# ESP32_Board.net
KiCad netlist of a schematic drawn in Altium Designer
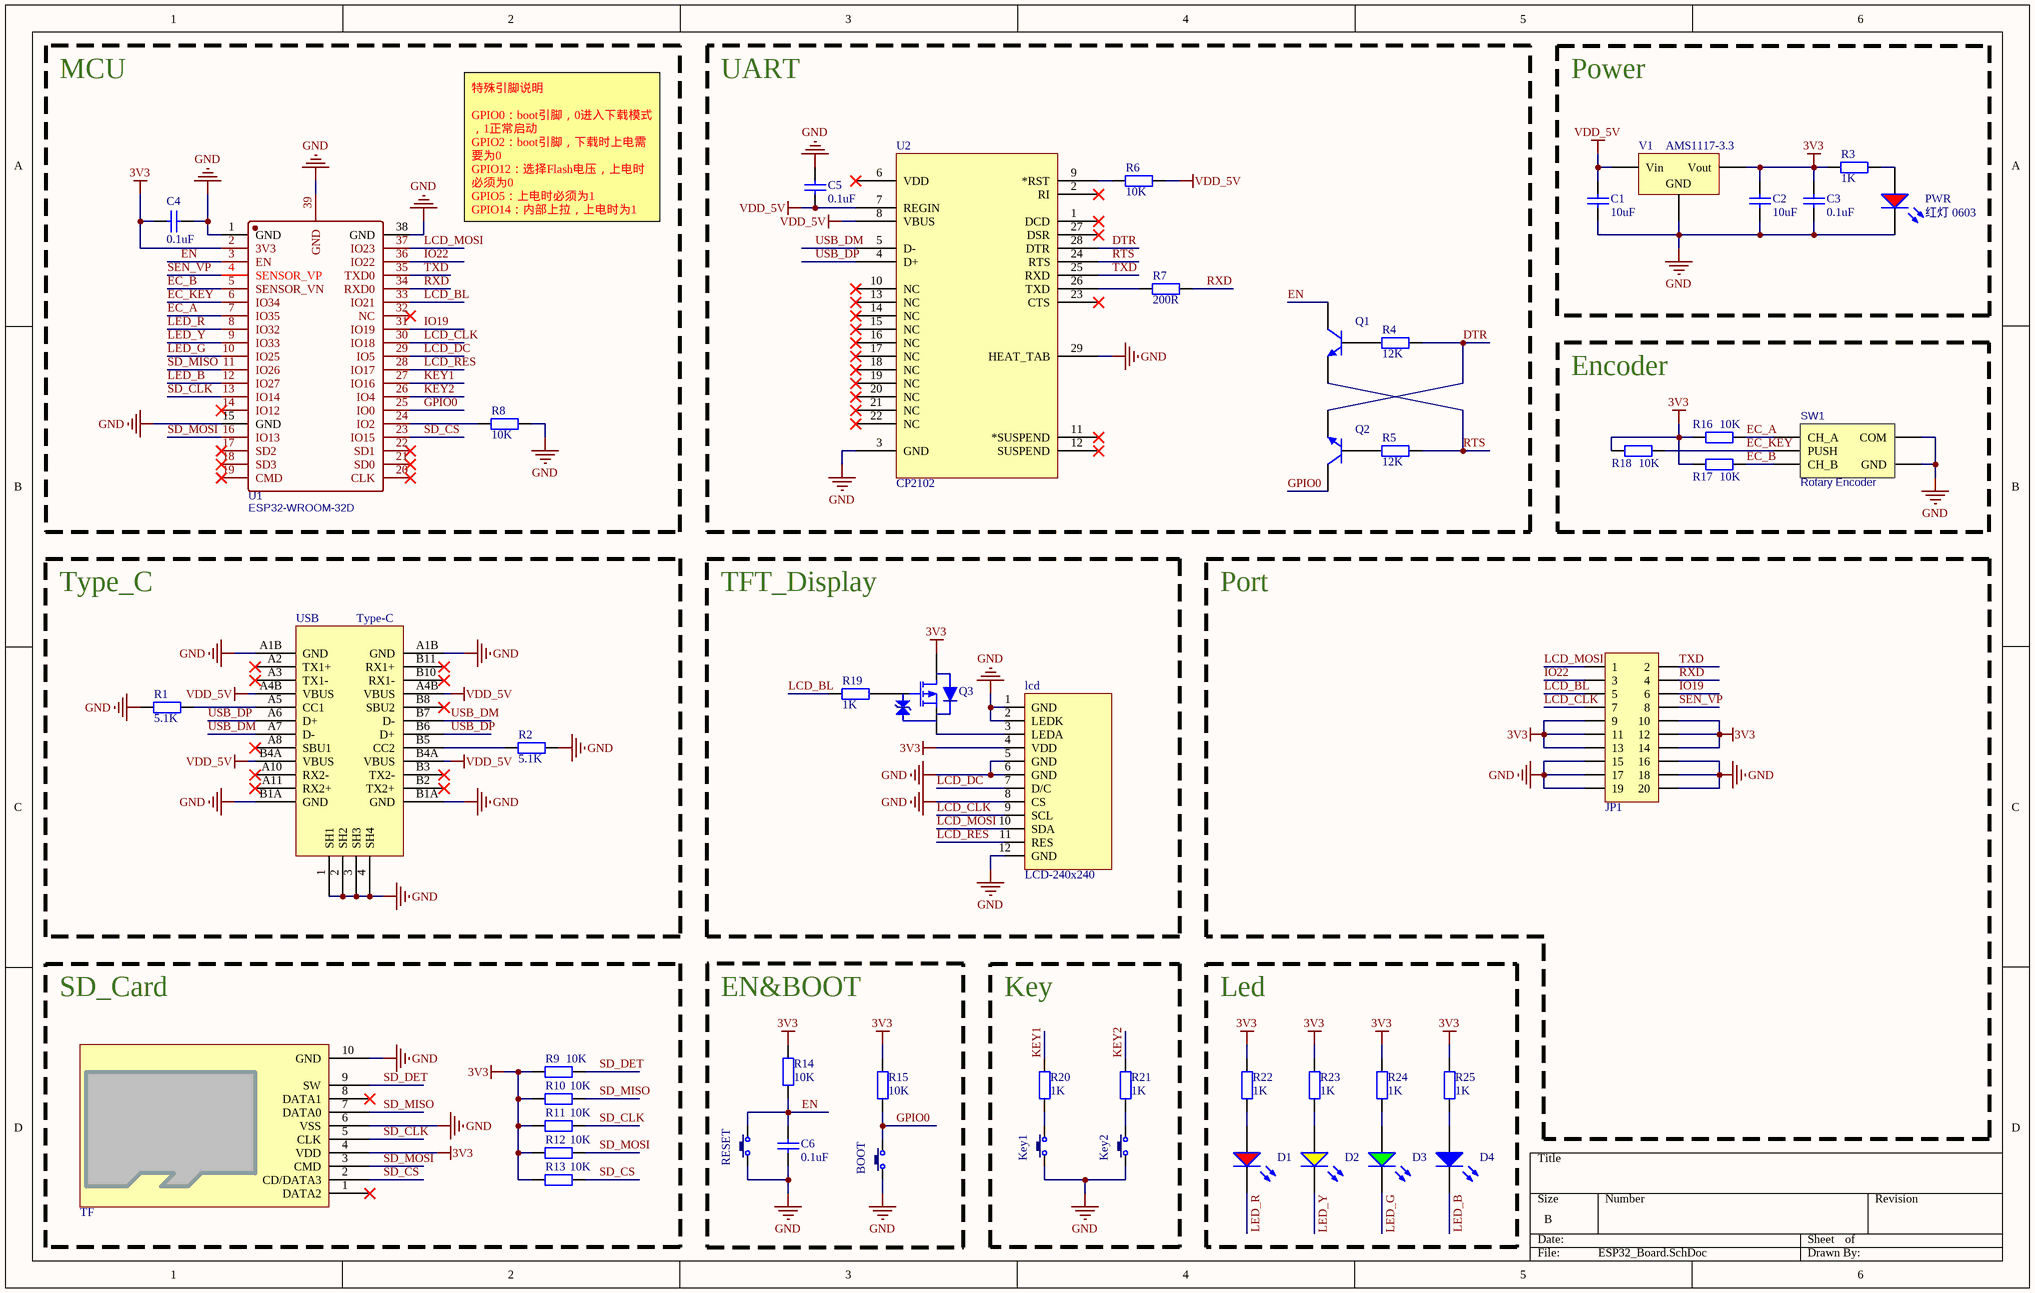
[diagram p0: ESP32_Board.SchDoc]

(export (version "E")
  (design (tool "Eeschema 10.0.6"))
  (components
    (comp (ref "BOOT")
      (value "3x6x5")
      (footprint "TSW SMD-6*6*5")
      (description "3x6轻触开关")
      (fields (field (name "版权归属") "源创客"))
      (libsource (lib "原理图库") (part "TSW 3x6"))
    )
    (comp (ref "C1")
      (value "10uF")
      (footprint "0603_C")
      (description "贴片电容")
      (libsource (lib "Miscellaneous Devices LC") (part "0603 1.2nF (122) 10% 50V"))
    )
    (comp (ref "C2")
      (value "10uF")
      (footprint "0603_C")
      (description "贴片电容")
      (libsource (lib "Miscellaneous Devices LC") (part "0603 1.2nF (122) 10% 50V"))
    )
    (comp (ref "C3")
      (value "0.1uF")
      (footprint "0603_C")
      (description "贴片电容")
      (libsource (lib "Miscellaneous Devices LC") (part "0603 1.2nF (122) 10% 50V"))
    )
    (comp (ref "C4")
      (value "0.1uF")
      (footprint "0603_C")
      (description "贴片电容")
      (libsource (lib "Miscellaneous Devices LC") (part "0603 1.2nF (122) 10% 50V"))
    )
    (comp (ref "C5")
      (value "0.1uF")
      (footprint "0603_C")
      (description "贴片电容")
      (libsource (lib "Miscellaneous Devices LC") (part "0603 100nF (104) 10% 50V"))
    )
    (comp (ref "C6")
      (value "0.1uF")
      (footprint "0603_C")
      (description "贴片电容")
      (libsource (lib "Miscellaneous Devices LC") (part "0603 10uF (106) 10% 10V"))
    )
    (comp (ref "D1")
      (value "红灯 0805")
      (footprint "0805_LED_S1")
      (description "发光二极管")
      (libsource (lib "Miscellaneous Devices LC") (part "0805 红灯"))
    )
    (comp (ref "D2")
      (value "黄灯 0805")
      (footprint "0805_LED_S1")
      (description "发光二极管")
      (libsource (lib "Miscellaneous Devices LC") (part "0805 黄灯"))
    )
    (comp (ref "D3")
      (value "翠绿 0805")
      (footprint "0805_LED_S1")
      (description "发光二极管")
      (libsource (lib "Miscellaneous Devices LC") (part "0805 翠绿"))
    )
    (comp (ref "D4")
      (value "蓝灯 0805")
      (footprint "0805_LED_S1")
      (description "发光二极管")
      (libsource (lib "Miscellaneous Devices LC") (part "0805 蓝灯"))
    )
    (comp (ref "JP1")
      (value "Header 2X10")
      (footprint "HDR2.54-M-LS-2x10P")
      (description "10*2P接插件")
      (fields (field (name "版权归属") "源创客"))
      (libsource (lib "Schlib1") (part "Header 10X2"))
    )
    (comp (ref "Key1")
      (value "3x6x5")
      (footprint "TSW SMD-6*6*5")
      (description "3x6轻触开关")
      (fields (field (name "版权归属") "源创客"))
      (libsource (lib "原理图库") (part "TSW 3x6"))
    )
    (comp (ref "Key2")
      (value "3x6x5")
      (footprint "TSW SMD-6*6*5")
      (description "3x6轻触开关")
      (fields (field (name "版权归属") "源创客"))
      (libsource (lib "原理图库") (part "TSW 3x6"))
    )
    (comp (ref "lcd")
      (value "LCD-240x240")
      (footprint "LCD-240x240-NoHole")
      (description "显示屏")
      (libsource (lib "Schlib1") (part "LCD-240x240"))
    )
    (comp (ref "PWR")
      (value "红灯 0603")
      (footprint "0603_LED_S1")
      (description "发光二极管")
      (libsource (lib "Miscellaneous Devices LC") (part "0603 红灯"))
    )
    (comp (ref "Q1")
      (value "SS8050 Y1")
      (footprint "SOT-23(SOT-23-3)")
      (description "三极管")
      (libsource (lib "Miscellaneous Devices LC") (part "SOT-23 SS8050 Y1"))
    )
    (comp (ref "Q2")
      (value "SS8050 Y1")
      (footprint "SOT-23(SOT-23-3)")
      (description "三极管")
      (libsource (lib "Miscellaneous Devices LC") (part "SOT-23 SS8050 Y1"))
    )
    (comp (ref "Q3")
      (value "AO3415A")
      (footprint "SOT23-3")
      (description "MOSFET")
      (fields (field (name "PUBLISHER") "Altium Limited"))
      (libsource (lib "Schlib1") (part "AO3415A"))
    )
    (comp (ref "R1")
      (value "5.1K")
      (footprint "0603_R")
      (description "贴片电阻")
      (libsource (lib "Miscellaneous Devices LC") (part "0603 1.1KΩ (1101) 1%"))
    )
    (comp (ref "R2")
      (value "5.1K")
      (footprint "0603_R")
      (description "贴片电阻")
      (libsource (lib "Miscellaneous Devices LC") (part "0603 1.1KΩ (1101) 1%"))
    )
    (comp (ref "R3")
      (value "1K")
      (footprint "0603_R")
      (description "贴片电阻")
      (libsource (lib "Miscellaneous Devices LC") (part "0603 110KΩ (1103) 1%"))
    )
    (comp (ref "R4")
      (value "12K")
      (footprint "0603_R")
      (description "贴片电阻")
      (libsource (lib "Miscellaneous Devices LC") (part "0603 1.2KΩ (1201) 1%"))
    )
    (comp (ref "R5")
      (value "12K")
      (footprint "0603_R")
      (description "贴片电阻")
      (libsource (lib "Miscellaneous Devices LC") (part "0603 1.2KΩ (1201) 1%"))
    )
    (comp (ref "R6")
      (value "10K")
      (footprint "0603_R")
      (description "贴片电阻")
      (libsource (lib "Miscellaneous Devices LC") (part "0603 1.2KΩ (1201) 1%"))
    )
    (comp (ref "R7")
      (value "200R")
      (footprint "0603_R")
      (description "贴片电阻")
      (libsource (lib "Miscellaneous Devices LC") (part "0603 1.2KΩ (1201) 1%"))
    )
    (comp (ref "R8")
      (value "10K")
      (footprint "0603_R")
      (description "贴片电阻")
      (libsource (lib "Miscellaneous Devices LC") (part "0603 1.5KΩ (1501) 1%"))
    )
    (comp (ref "R9")
      (value "10K")
      (footprint "0603_R")
      (description "贴片电阻")
      (libsource (lib "Miscellaneous Devices LC") (part "0603 1.8MΩ (1804) 1%"))
    )
    (comp (ref "R10")
      (value "10K")
      (footprint "0603_R")
      (description "贴片电阻")
      (libsource (lib "Miscellaneous Devices LC") (part "0603 1.8MΩ (1804) 1%"))
    )
    (comp (ref "R11")
      (value "10K")
      (footprint "0603_R")
      (description "贴片电阻")
      (libsource (lib "Miscellaneous Devices LC") (part "0603 1.8MΩ (1804) 1%"))
    )
    (comp (ref "R12")
      (value "10K")
      (footprint "0603_R")
      (description "贴片电阻")
      (libsource (lib "Miscellaneous Devices LC") (part "0603 1.8MΩ (1804) 1%"))
    )
    (comp (ref "R13")
      (value "10K")
      (footprint "0603_R")
      (description "贴片电阻")
      (libsource (lib "Miscellaneous Devices LC") (part "0603 1.8MΩ (1804) 1%"))
    )
    (comp (ref "R14")
      (value "10K")
      (footprint "0603_R")
      (description "贴片电阻")
      (libsource (lib "Miscellaneous Devices LC") (part "0603 100KΩ (1003) 1%"))
    )
    (comp (ref "R15")
      (value "10K")
      (footprint "0603_R")
      (description "贴片电阻")
      (libsource (lib "") (part "0603 1.5KΩ (1501) 1%_1"))
    )
    (comp (ref "R16")
      (value "10K")
      (footprint "0603_R")
      (description "贴片电阻")
      (libsource (lib "Miscellaneous Devices LC") (part "0603 1.8MΩ (1804) 1%"))
    )
    (comp (ref "R17")
      (value "10K")
      (footprint "0603_R")
      (description "贴片电阻")
      (libsource (lib "Miscellaneous Devices LC") (part "0603 1.8MΩ (1804) 1%"))
    )
    (comp (ref "R18")
      (value "10K")
      (footprint "0603_R")
      (description "贴片电阻")
      (libsource (lib "Miscellaneous Devices LC") (part "0603 1.8MΩ (1804) 1%"))
    )
    (comp (ref "R19")
      (value "1K")
      (footprint "0603_R")
      (description "贴片电阻")
      (libsource (lib "Miscellaneous Devices LC") (part "0603 1.2KΩ (1201) 1%"))
    )
    (comp (ref "R20")
      (value "1K")
      (footprint "0603_R")
      (description "贴片电阻")
      (libsource (lib "") (part "0603 1.2KΩ (1201) 1%_2"))
    )
    (comp (ref "R21")
      (value "1K")
      (footprint "0603_R")
      (description "贴片电阻")
      (libsource (lib "") (part "0603 1.2KΩ (1201) 1%_2"))
    )
    (comp (ref "R22")
      (value "1K")
      (footprint "0603_R")
      (description "贴片电阻")
      (libsource (lib "") (part "0603 1.2KΩ (1201) 1%_1"))
    )
    (comp (ref "R23")
      (value "1K")
      (footprint "0603_R")
      (description "贴片电阻")
      (libsource (lib "") (part "0603 1.2KΩ (1201) 1%_1"))
    )
    (comp (ref "R24")
      (value "1K")
      (footprint "0603_R")
      (description "贴片电阻")
      (libsource (lib "") (part "0603 1.2KΩ (1201) 1%_1"))
    )
    (comp (ref "R25")
      (value "1K")
      (footprint "0603_R")
      (description "贴片电阻")
      (libsource (lib "") (part "0603 1.2KΩ (1201) 1%_1"))
    )
    (comp (ref "RESET")
      (value "3x6x5")
      (footprint "SW")
      (description "3x6轻触开关")
      (fields (field (name "版权归属") "源创客"))
      (libsource (lib "原理图库") (part "TSW 3x6"))
    )
    (comp (ref "SW1")
      (value "Rotary Encoder")
      (footprint "SIQ-02FVS3")
      (fields
        (field (name "BOM_SUPPLIER PART") "C1322543")
        (field (name "BOM_MANUFACTURER PART") "EC11E1534443")
        (field (name "CONTRIBUTOR") "LCSC")
      )
      (libsource (lib "Schlib1") (part "Rotary Encoder"))
    )
    (comp (ref "TF")
      (value "TF")
      (footprint "Micro SD")
      (description "8脚自弹")
      (libsource (lib "原理图库") (part "TF卡座"))
    )
    (comp (ref "U1")
      (value "ESP32-WROOM-32D")
      (footprint "WIFI-SMD_ESP32-WROOM-32E")
      (fields
        (field (name "BOM_SUPPLIER PART") "C701342")
        (field (name "BOM_MANUFACTURER PART") "ESP32-WROOM-32E(8MB)")
        (field (name "CONTRIBUTOR") "LCSC")
      )
      (libsource (lib "原理图库") (part "ESP32_WROOM_32D"))
    )
    (comp (ref "U2")
      (value "CP2102")
      (footprint "QFN28 5x5_N")
      (description "USB转TTL")
      (libsource (lib "原理图库") (part "CP2102"))
    )
    (comp (ref "USB")
      (value "Type-C")
      (footprint "Type-C-TOP")
      (libsource (lib "原理图库") (part "USB-Type-C-TOP"))
    )
    (comp (ref "V1")
      (value "AMS1117-3.3")
      (footprint "SOT-89")
      (description "低压差线性稳压(LDO)")
      (libsource (lib "Miscellaneous Devices LC") (part "SOT-223 AMS1117-3.3"))
    )
  )
  (nets
    (net (code "1") (name "/DTR") (class "Default")
      (node (ref "Q2") (pin "2") (pinfunction "E_2") (pintype "passive"))
      (node (ref "R4") (pin "2") (pinfunction "2_2") (pintype "passive"))
      (node (ref "U2") (pin "28") (pinfunction "DTR_28") (pintype "passive"))
    )
    (net (code "2") (name "/EC_A") (class "Default")
      (node (ref "R16") (pin "2") (pinfunction "2_2") (pintype "passive"))
      (node (ref "SW1") (pin "1") (pinfunction "CH_A_1") (pintype "passive"))
      (node (ref "U1") (pin "7") (pinfunction "IO35_7") (pintype "passive"))
    )
    (net (code "3") (name "/EC_B") (class "Default")
      (node (ref "R17") (pin "2") (pinfunction "2_2") (pintype "passive"))
      (node (ref "SW1") (pin "4") (pinfunction "CH_B_4") (pintype "passive"))
      (node (ref "U1") (pin "5") (pinfunction "SENSOR_VN_5") (pintype "passive"))
    )
    (net (code "4") (name "/EC_KEY") (class "Default")
      (node (ref "R18") (pin "2") (pinfunction "2_2") (pintype "passive"))
      (node (ref "SW1") (pin "2") (pinfunction "PUSH_2") (pintype "passive"))
      (node (ref "U1") (pin "6") (pinfunction "IO34_6") (pintype "passive"))
    )
    (net (code "5") (name "/EN") (class "Default")
      (node (ref "C6") (pin "2") (pinfunction "2_2") (pintype "passive"))
      (node (ref "Q1") (pin "3") (pinfunction "C_3") (pintype "passive"))
      (node (ref "R14") (pin "1") (pinfunction "1_1") (pintype "passive"))
      (node (ref "RESET") (pin "2") (pinfunction "2_2") (pintype "passive"))
      (node (ref "U1") (pin "3") (pinfunction "EN_3") (pintype "passive"))
    )
    (net (code "6") (name "/GPIO0") (class "Default")
      (node (ref "BOOT") (pin "2") (pinfunction "2_2") (pintype "passive"))
      (node (ref "Q2") (pin "3") (pinfunction "C_3") (pintype "passive"))
      (node (ref "R15") (pin "1") (pinfunction "1_1") (pintype "passive"))
      (node (ref "U1") (pin "25") (pinfunction "IO0_25") (pintype "passive"))
    )
    (net (code "7") (name "/IO19") (class "Default")
      (node (ref "JP1") (pin "6") (pinfunction "6_6") (pintype "passive"))
      (node (ref "U1") (pin "31") (pinfunction "IO19_31") (pintype "passive"))
    )
    (net (code "8") (name "/IO22") (class "Default")
      (node (ref "JP1") (pin "3") (pinfunction "3_3") (pintype "passive"))
      (node (ref "U1") (pin "36") (pinfunction "IO22_36") (pintype "passive"))
    )
    (net (code "9") (name "/KEY1") (class "Default")
      (node (ref "R20") (pin "2") (pinfunction "2_2") (pintype "passive"))
      (node (ref "U1") (pin "27") (pinfunction "IO16_27") (pintype "passive"))
    )
    (net (code "10") (name "/KEY2") (class "Default")
      (node (ref "R21") (pin "2") (pinfunction "2_2") (pintype "passive"))
      (node (ref "U1") (pin "26") (pinfunction "IO4_26") (pintype "passive"))
    )
    (net (code "11") (name "/LCD_BL") (class "Default")
      (node (ref "JP1") (pin "5") (pinfunction "5_5") (pintype "passive"))
      (node (ref "R19") (pin "1") (pinfunction "1_1") (pintype "passive"))
      (node (ref "U1") (pin "33") (pinfunction "IO21_33") (pintype "passive"))
    )
    (net (code "12") (name "/LCD_CLK") (class "Default")
      (node (ref "JP1") (pin "7") (pinfunction "7_7") (pintype "passive"))
      (node (ref "U1") (pin "30") (pinfunction "IO18_30") (pintype "passive"))
      (node (ref "lcd") (pin "9") (pinfunction "SCL_9") (pintype "passive"))
    )
    (net (code "13") (name "/LCD_DC") (class "Default")
      (node (ref "U1") (pin "29") (pinfunction "IO5_29") (pintype "passive"))
      (node (ref "lcd") (pin "7") (pinfunction "D/C_7") (pintype "passive"))
    )
    (net (code "14") (name "/LCD_MOSI") (class "Default")
      (node (ref "JP1") (pin "1") (pinfunction "1_1") (pintype "passive"))
      (node (ref "U1") (pin "37") (pinfunction "IO23_37") (pintype "passive"))
      (node (ref "lcd") (pin "10") (pinfunction "SDA_10") (pintype "passive"))
    )
    (net (code "15") (name "/LCD_RES") (class "Default")
      (node (ref "U1") (pin "28") (pinfunction "IO17_28") (pintype "passive"))
      (node (ref "lcd") (pin "11") (pinfunction "RES_11") (pintype "passive"))
    )
    (net (code "16") (name "/LED_B") (class "Default")
      (node (ref "D4") (pin "K") (pinfunction "K_K") (pintype "passive"))
      (node (ref "U1") (pin "12") (pinfunction "IO27_12") (pintype "passive"))
    )
    (net (code "17") (name "/LED_G") (class "Default")
      (node (ref "D3") (pin "K") (pinfunction "K_K") (pintype "passive"))
      (node (ref "U1") (pin "10") (pinfunction "IO25_10") (pintype "passive"))
    )
    (net (code "18") (name "/LED_R") (class "Default")
      (node (ref "D1") (pin "K") (pinfunction "K_K") (pintype "passive"))
      (node (ref "U1") (pin "8") (pinfunction "IO32_8") (pintype "passive"))
    )
    (net (code "19") (name "/LED_Y") (class "Default")
      (node (ref "D2") (pin "K") (pinfunction "K_K") (pintype "passive"))
      (node (ref "U1") (pin "9") (pinfunction "IO33_9") (pintype "passive"))
    )
    (net (code "20") (name "/RTS") (class "Default")
      (node (ref "Q1") (pin "2") (pinfunction "E_2") (pintype "passive"))
      (node (ref "R5") (pin "2") (pinfunction "2_2") (pintype "passive"))
      (node (ref "U2") (pin "24") (pinfunction "RTS_24") (pintype "passive"))
    )
    (net (code "21") (name "/RXD") (class "Default")
      (node (ref "JP1") (pin "4") (pinfunction "4_4") (pintype "passive"))
      (node (ref "R7") (pin "2") (pinfunction "2_2") (pintype "passive"))
      (node (ref "U1") (pin "34") (pinfunction "RXD0_34") (pintype "passive"))
    )
    (net (code "22") (name "/SD_CLK") (class "Default")
      (node (ref "R11") (pin "2") (pinfunction "2_2") (pintype "passive"))
      (node (ref "TF") (pin "5") (pinfunction "CLK_5") (pintype "passive"))
      (node (ref "U1") (pin "13") (pinfunction "IO14_13") (pintype "passive"))
    )
    (net (code "23") (name "/SD_CS") (class "Default")
      (node (ref "R13") (pin "2") (pinfunction "2_2") (pintype "passive"))
      (node (ref "TF") (pin "2") (pinfunction "CD/DATA3_2") (pintype "passive"))
      (node (ref "U1") (pin "23") (pinfunction "IO15_23") (pintype "passive"))
    )
    (net (code "24") (name "/SD_DET") (class "Default")
      (node (ref "R9") (pin "2") (pinfunction "2_2") (pintype "passive"))
      (node (ref "TF") (pin "9") (pinfunction "SW_9") (pintype "passive"))
    )
    (net (code "25") (name "/SD_MISO") (class "Default")
      (node (ref "R10") (pin "2") (pinfunction "2_2") (pintype "passive"))
      (node (ref "TF") (pin "7") (pinfunction "DATA0_7") (pintype "passive"))
      (node (ref "U1") (pin "11") (pinfunction "IO26_11") (pintype "passive"))
    )
    (net (code "26") (name "/SD_MOSI") (class "Default")
      (node (ref "R12") (pin "2") (pinfunction "2_2") (pintype "passive"))
      (node (ref "TF") (pin "3") (pinfunction "CMD_3") (pintype "passive"))
      (node (ref "U1") (pin "16") (pinfunction "IO13_16") (pintype "passive"))
    )
    (net (code "27") (name "/SEN_VP") (class "Default")
      (node (ref "JP1") (pin "8") (pinfunction "8_8") (pintype "passive"))
      (node (ref "U1") (pin "4") (pinfunction "SENSOR_VP_4") (pintype "passive"))
    )
    (net (code "28") (name "/TXD") (class "Default")
      (node (ref "JP1") (pin "2") (pinfunction "2_2") (pintype "passive"))
      (node (ref "U1") (pin "35") (pinfunction "TXD0_35") (pintype "passive"))
      (node (ref "U2") (pin "25") (pinfunction "RXD_25") (pintype "passive"))
    )
    (net (code "29") (name "/USB_DM") (class "Default")
      (node (ref "U2") (pin "5") (pinfunction "D-_5") (pintype "passive"))
      (node (ref "USB") (pin "A7") (pinfunction "D-_A7") (pintype "passive"))
      (node (ref "USB") (pin "B7") (pinfunction "D-_B7") (pintype "passive"))
    )
    (net (code "30") (name "/USB_DP") (class "Default")
      (node (ref "U2") (pin "4") (pinfunction "D+_4") (pintype "passive"))
      (node (ref "USB") (pin "A6") (pinfunction "D+_A6") (pintype "passive"))
      (node (ref "USB") (pin "B6") (pinfunction "D+_B6") (pintype "passive"))
    )
    (net (code "31") (name "3V3") (class "Default")
      (node (ref "C2") (pin "2") (pinfunction "2_2") (pintype "passive"))
      (node (ref "C3") (pin "2") (pinfunction "2_2") (pintype "passive"))
      (node (ref "C4") (pin "2") (pinfunction "2_2") (pintype "passive"))
      (node (ref "JP1") (pin "10") (pinfunction "10_10") (pintype "passive"))
      (node (ref "JP1") (pin "11") (pinfunction "11_11") (pintype "passive"))
      (node (ref "JP1") (pin "12") (pinfunction "12_12") (pintype "passive"))
      (node (ref "JP1") (pin "13") (pinfunction "13_13") (pintype "passive"))
      (node (ref "JP1") (pin "14") (pinfunction "14_14") (pintype "passive"))
      (node (ref "JP1") (pin "9") (pinfunction "9_9") (pintype "passive"))
      (node (ref "Q3") (pin "3") (pinfunction "D_3") (pintype "passive"))
      (node (ref "R10") (pin "1") (pinfunction "1_1") (pintype "passive"))
      (node (ref "R11") (pin "1") (pinfunction "1_1") (pintype "passive"))
      (node (ref "R12") (pin "1") (pinfunction "1_1") (pintype "passive"))
      (node (ref "R13") (pin "1") (pinfunction "1_1") (pintype "passive"))
      (node (ref "R14") (pin "2") (pinfunction "2_2") (pintype "passive"))
      (node (ref "R15") (pin "2") (pinfunction "2_2") (pintype "passive"))
      (node (ref "R16") (pin "1") (pinfunction "1_1") (pintype "passive"))
      (node (ref "R17") (pin "1") (pinfunction "1_1") (pintype "passive"))
      (node (ref "R18") (pin "1") (pinfunction "1_1") (pintype "passive"))
      (node (ref "R22") (pin "1") (pinfunction "1_1") (pintype "passive"))
      (node (ref "R23") (pin "1") (pinfunction "1_1") (pintype "passive"))
      (node (ref "R24") (pin "1") (pinfunction "1_1") (pintype "passive"))
      (node (ref "R25") (pin "1") (pinfunction "1_1") (pintype "passive"))
      (node (ref "R3") (pin "1") (pinfunction "1_1") (pintype "passive"))
      (node (ref "R9") (pin "1") (pinfunction "1_1") (pintype "passive"))
      (node (ref "TF") (pin "4") (pinfunction "VDD_4") (pintype "passive"))
      (node (ref "U1") (pin "2") (pinfunction "3V3_2") (pintype "passive"))
      (node (ref "V1") (pin "2") (pinfunction "Vout_2") (pintype "passive"))
      (node (ref "lcd") (pin "4") (pinfunction "VDD_4") (pintype "passive"))
    )
    (net (code "32") (name "GND") (class "Default")
      (node (ref "BOOT") (pin "1") (pinfunction "1_1") (pintype "passive"))
      (node (ref "C1") (pin "1") (pinfunction "1_1") (pintype "passive"))
      (node (ref "C2") (pin "1") (pinfunction "1_1") (pintype "passive"))
      (node (ref "C3") (pin "1") (pinfunction "1_1") (pintype "passive"))
      (node (ref "C4") (pin "1") (pinfunction "1_1") (pintype "passive"))
      (node (ref "C5") (pin "2") (pinfunction "2_2") (pintype "passive"))
      (node (ref "C6") (pin "1") (pinfunction "1_1") (pintype "passive"))
      (node (ref "JP1") (pin "15") (pinfunction "15_15") (pintype "passive"))
      (node (ref "JP1") (pin "16") (pinfunction "16_16") (pintype "passive"))
      (node (ref "JP1") (pin "17") (pinfunction "17_17") (pintype "passive"))
      (node (ref "JP1") (pin "18") (pinfunction "18_18") (pintype "passive"))
      (node (ref "JP1") (pin "19") (pinfunction "19_19") (pintype "passive"))
      (node (ref "JP1") (pin "20") (pinfunction "20_20") (pintype "passive"))
      (node (ref "Key1") (pin "1") (pinfunction "1_1") (pintype "passive"))
      (node (ref "Key2") (pin "1") (pinfunction "1_1") (pintype "passive"))
      (node (ref "PWR") (pin "K") (pinfunction "K_K") (pintype "passive"))
      (node (ref "R1") (pin "1") (pinfunction "1_1") (pintype "passive"))
      (node (ref "R2") (pin "2") (pinfunction "2_2") (pintype "passive"))
      (node (ref "R8") (pin "2") (pinfunction "2_2") (pintype "passive"))
      (node (ref "RESET") (pin "1") (pinfunction "1_1") (pintype "passive"))
      (node (ref "SW1") (pin "3") (pinfunction "COM_3") (pintype "passive"))
      (node (ref "SW1") (pin "5") (pinfunction "GND_5") (pintype "passive"))
      (node (ref "TF") (pin "10") (pinfunction "GND_10") (pintype "passive"))
      (node (ref "TF") (pin "6") (pinfunction "VSS_6") (pintype "passive"))
      (node (ref "U1") (pin "1") (pinfunction "GND_1") (pintype "passive"))
      (node (ref "U1") (pin "15") (pinfunction "GND_15") (pintype "passive"))
      (node (ref "U1") (pin "38") (pinfunction "GND_38") (pintype "passive"))
      (node (ref "U1") (pin "39") (pinfunction "GND_39") (pintype "passive"))
      (node (ref "U2") (pin "29") (pinfunction "HEAT_TAB_29") (pintype "passive"))
      (node (ref "U2") (pin "3") (pinfunction "GND_3") (pintype "passive"))
      (node (ref "USB") (pin "1") (pinfunction "SH1_1") (pintype "passive"))
      (node (ref "USB") (pin "2") (pinfunction "SH2_2") (pintype "passive"))
      (node (ref "USB") (pin "3") (pinfunction "SH3_3") (pintype "passive"))
      (node (ref "USB") (pin "4") (pinfunction "SH4_4") (pintype "passive"))
      (node (ref "USB") (pin "A1B") (pinfunction "GND_A1B") (pintype "passive"))
      (node (ref "USB") (pin "B1A") (pinfunction "GND_B1A") (pintype "passive"))
      (node (ref "V1") (pin "1") (pinfunction "GND_1") (pintype "passive"))
      (node (ref "lcd") (pin "1") (pinfunction "GND_1") (pintype "passive"))
      (node (ref "lcd") (pin "12") (pinfunction "GND_12") (pintype "passive"))
      (node (ref "lcd") (pin "2") (pinfunction "LEDK_2") (pintype "passive"))
      (node (ref "lcd") (pin "5") (pinfunction "GND_5") (pintype "passive"))
      (node (ref "lcd") (pin "6") (pinfunction "GND_6") (pintype "passive"))
      (node (ref "lcd") (pin "8") (pinfunction "CS_8") (pintype "passive"))
    )
    (net (code "33") (name "Net-(D1-PadA)") (class "Default")
      (node (ref "D1") (pin "A") (pinfunction "A_A") (pintype "passive"))
      (node (ref "R22") (pin "2") (pinfunction "2_2") (pintype "passive"))
    )
    (net (code "34") (name "Net-(D2-PadA)") (class "Default")
      (node (ref "D2") (pin "A") (pinfunction "A_A") (pintype "passive"))
      (node (ref "R23") (pin "2") (pinfunction "2_2") (pintype "passive"))
    )
    (net (code "35") (name "Net-(D3-PadA)") (class "Default")
      (node (ref "D3") (pin "A") (pinfunction "A_A") (pintype "passive"))
      (node (ref "R24") (pin "2") (pinfunction "2_2") (pintype "passive"))
    )
    (net (code "36") (name "Net-(D4-PadA)") (class "Default")
      (node (ref "D4") (pin "A") (pinfunction "A_A") (pintype "passive"))
      (node (ref "R25") (pin "2") (pinfunction "2_2") (pintype "passive"))
    )
    (net (code "37") (name "Net-(Key1-Pad2)") (class "Default")
      (node (ref "Key1") (pin "2") (pinfunction "2_2") (pintype "passive"))
      (node (ref "R20") (pin "1") (pinfunction "1_1") (pintype "passive"))
    )
    (net (code "38") (name "Net-(Key2-Pad2)") (class "Default")
      (node (ref "Key2") (pin "2") (pinfunction "2_2") (pintype "passive"))
      (node (ref "R21") (pin "1") (pinfunction "1_1") (pintype "passive"))
    )
    (net (code "39") (name "Net-(PWR-PadA)") (class "Default")
      (node (ref "PWR") (pin "A") (pinfunction "A_A") (pintype "passive"))
      (node (ref "R3") (pin "2") (pinfunction "2_2") (pintype "passive"))
    )
    (net (code "40") (name "Net-(Q1-B)") (class "Default")
      (node (ref "Q1") (pin "1") (pinfunction "B_1") (pintype "passive"))
      (node (ref "R4") (pin "1") (pinfunction "1_1") (pintype "passive"))
    )
    (net (code "41") (name "Net-(Q2-B)") (class "Default")
      (node (ref "Q2") (pin "1") (pinfunction "B_1") (pintype "passive"))
      (node (ref "R5") (pin "1") (pinfunction "1_1") (pintype "passive"))
    )
    (net (code "42") (name "Net-(Q3-G)") (class "Default")
      (node (ref "Q3") (pin "1") (pinfunction "G_1") (pintype "passive"))
      (node (ref "R19") (pin "2") (pinfunction "2_2") (pintype "passive"))
    )
    (net (code "43") (name "Net-(Q3-S)") (class "Default")
      (node (ref "Q3") (pin "2") (pinfunction "S_2") (pintype "passive"))
      (node (ref "lcd") (pin "3") (pinfunction "LEDA_3") (pintype "passive"))
    )
    (net (code "44") (name "Net-(U1-IO2)") (class "Default")
      (node (ref "R8") (pin "1") (pinfunction "1_1") (pintype "passive"))
      (node (ref "U1") (pin "24") (pinfunction "IO2_24") (pintype "passive"))
    )
    (net (code "45") (name "Net-(U2-*RST)") (class "Default")
      (node (ref "R6") (pin "1") (pinfunction "1_1") (pintype "passive"))
      (node (ref "U2") (pin "9") (pinfunction "*RST_9") (pintype "passive"))
    )
    (net (code "46") (name "Net-(U2-TXD)") (class "Default")
      (node (ref "R7") (pin "1") (pinfunction "1_1") (pintype "passive"))
      (node (ref "U2") (pin "26") (pinfunction "TXD_26") (pintype "passive"))
    )
    (net (code "47") (name "Net-(USB-CC1)") (class "Default")
      (node (ref "R1") (pin "2") (pinfunction "2_2") (pintype "passive"))
      (node (ref "USB") (pin "A5") (pinfunction "CC1_A5") (pintype "passive"))
    )
    (net (code "48") (name "Net-(USB-CC2)") (class "Default")
      (node (ref "R2") (pin "1") (pinfunction "1_1") (pintype "passive"))
      (node (ref "USB") (pin "B5") (pinfunction "CC2_B5") (pintype "passive"))
    )
    (net (code "49") (name "VDD_5V") (class "Default")
      (node (ref "C1") (pin "2") (pinfunction "2_2") (pintype "passive"))
      (node (ref "C5") (pin "1") (pinfunction "1_1") (pintype "passive"))
      (node (ref "R6") (pin "2") (pinfunction "2_2") (pintype "passive"))
      (node (ref "U2") (pin "7") (pinfunction "REGIN_7") (pintype "passive"))
      (node (ref "U2") (pin "8") (pinfunction "VBUS_8") (pintype "passive"))
      (node (ref "USB") (pin "A4B") (pinfunction "VBUS_A4B") (pintype "passive"))
      (node (ref "USB") (pin "B4A") (pinfunction "VBUS_B4A") (pintype "passive"))
      (node (ref "V1") (pin "3") (pinfunction "Vin_3") (pintype "passive"))
    )
    (net (code "50") (name "unconnected-(TF-DATA1-Pad8)") (class "Default")
      (node (ref "TF") (pin "8") (pinfunction "DATA1_8") (pintype "passive+no_connect"))
    )
    (net (code "51") (name "unconnected-(TF-DATA2-Pad1)") (class "Default")
      (node (ref "TF") (pin "1") (pinfunction "DATA2_1") (pintype "passive+no_connect"))
    )
    (net (code "52") (name "unconnected-(U1-CLK-Pad20)") (class "Default")
      (node (ref "U1") (pin "20") (pinfunction "CLK_20") (pintype "passive+no_connect"))
    )
    (net (code "53") (name "unconnected-(U1-CMD-Pad19)") (class "Default")
      (node (ref "U1") (pin "19") (pinfunction "CMD_19") (pintype "passive+no_connect"))
    )
    (net (code "54") (name "unconnected-(U1-IO12-Pad14)") (class "Default")
      (node (ref "U1") (pin "14") (pinfunction "IO12_14") (pintype "passive+no_connect"))
    )
    (net (code "55") (name "unconnected-(U1-NC-Pad32)") (class "Default")
      (node (ref "U1") (pin "32") (pinfunction "NC_32") (pintype "passive+no_connect"))
    )
    (net (code "56") (name "unconnected-(U1-SD0-Pad21)") (class "Default")
      (node (ref "U1") (pin "21") (pinfunction "SD0_21") (pintype "passive+no_connect"))
    )
    (net (code "57") (name "unconnected-(U1-SD1-Pad22)") (class "Default")
      (node (ref "U1") (pin "22") (pinfunction "SD1_22") (pintype "passive+no_connect"))
    )
    (net (code "58") (name "unconnected-(U1-SD2-Pad17)") (class "Default")
      (node (ref "U1") (pin "17") (pinfunction "SD2_17") (pintype "passive+no_connect"))
    )
    (net (code "59") (name "unconnected-(U1-SD3-Pad18)") (class "Default")
      (node (ref "U1") (pin "18") (pinfunction "SD3_18") (pintype "passive+no_connect"))
    )
    (net (code "60") (name "unconnected-(U2-*SUSPEND-Pad11)") (class "Default")
      (node (ref "U2") (pin "11") (pinfunction "*SUSPEND_11") (pintype "passive+no_connect"))
    )
    (net (code "61") (name "unconnected-(U2-CTS-Pad23)") (class "Default")
      (node (ref "U2") (pin "23") (pinfunction "CTS_23") (pintype "passive+no_connect"))
    )
    (net (code "62") (name "unconnected-(U2-DCD-Pad1)") (class "Default")
      (node (ref "U2") (pin "1") (pinfunction "DCD_1") (pintype "passive+no_connect"))
    )
    (net (code "63") (name "unconnected-(U2-DSR-Pad27)") (class "Default")
      (node (ref "U2") (pin "27") (pinfunction "DSR_27") (pintype "passive+no_connect"))
    )
    (net (code "64") (name "unconnected-(U2-NC-Pad10)") (class "Default")
      (node (ref "U2") (pin "10") (pinfunction "NC_10") (pintype "passive+no_connect"))
    )
    (net (code "65") (name "unconnected-(U2-NC-Pad13)") (class "Default")
      (node (ref "U2") (pin "13") (pinfunction "NC_13") (pintype "passive+no_connect"))
    )
    (net (code "66") (name "unconnected-(U2-NC-Pad14)") (class "Default")
      (node (ref "U2") (pin "14") (pinfunction "NC_14") (pintype "passive+no_connect"))
    )
    (net (code "67") (name "unconnected-(U2-NC-Pad15)") (class "Default")
      (node (ref "U2") (pin "15") (pinfunction "NC_15") (pintype "passive+no_connect"))
    )
    (net (code "68") (name "unconnected-(U2-NC-Pad16)") (class "Default")
      (node (ref "U2") (pin "16") (pinfunction "NC_16") (pintype "passive+no_connect"))
    )
    (net (code "69") (name "unconnected-(U2-NC-Pad17)") (class "Default")
      (node (ref "U2") (pin "17") (pinfunction "NC_17") (pintype "passive+no_connect"))
    )
    (net (code "70") (name "unconnected-(U2-NC-Pad18)") (class "Default")
      (node (ref "U2") (pin "18") (pinfunction "NC_18") (pintype "passive+no_connect"))
    )
    (net (code "71") (name "unconnected-(U2-NC-Pad19)") (class "Default")
      (node (ref "U2") (pin "19") (pinfunction "NC_19") (pintype "passive+no_connect"))
    )
    (net (code "72") (name "unconnected-(U2-NC-Pad20)") (class "Default")
      (node (ref "U2") (pin "20") (pinfunction "NC_20") (pintype "passive+no_connect"))
    )
    (net (code "73") (name "unconnected-(U2-NC-Pad21)") (class "Default")
      (node (ref "U2") (pin "21") (pinfunction "NC_21") (pintype "passive+no_connect"))
    )
    (net (code "74") (name "unconnected-(U2-NC-Pad22)") (class "Default")
      (node (ref "U2") (pin "22") (pinfunction "NC_22") (pintype "passive+no_connect"))
    )
    (net (code "75") (name "unconnected-(U2-RI-Pad2)") (class "Default")
      (node (ref "U2") (pin "2") (pinfunction "RI_2") (pintype "passive+no_connect"))
    )
    (net (code "76") (name "unconnected-(U2-SUSPEND-Pad12)") (class "Default")
      (node (ref "U2") (pin "12") (pinfunction "SUSPEND_12") (pintype "passive+no_connect"))
    )
    (net (code "77") (name "unconnected-(U2-VDD-Pad6)") (class "Default")
      (node (ref "U2") (pin "6") (pinfunction "VDD_6") (pintype "passive+no_connect"))
    )
    (net (code "78") (name "unconnected-(USB-RX1+-PadB11)") (class "Default")
      (node (ref "USB") (pin "B11") (pinfunction "RX1+_B11") (pintype "passive+no_connect"))
    )
    (net (code "79") (name "unconnected-(USB-RX1--PadB10)") (class "Default")
      (node (ref "USB") (pin "B10") (pinfunction "RX1-_B10") (pintype "passive+no_connect"))
    )
    (net (code "80") (name "unconnected-(USB-RX2+-PadA11)") (class "Default")
      (node (ref "USB") (pin "A11") (pinfunction "RX2+_A11") (pintype "passive+no_connect"))
    )
    (net (code "81") (name "unconnected-(USB-RX2--PadA10)") (class "Default")
      (node (ref "USB") (pin "A10") (pinfunction "RX2-_A10") (pintype "passive+no_connect"))
    )
    (net (code "82") (name "unconnected-(USB-SBU1-PadA8)") (class "Default")
      (node (ref "USB") (pin "A8") (pinfunction "SBU1_A8") (pintype "passive+no_connect"))
    )
    (net (code "83") (name "unconnected-(USB-SBU2-PadB8)") (class "Default")
      (node (ref "USB") (pin "B8") (pinfunction "SBU2_B8") (pintype "passive+no_connect"))
    )
    (net (code "84") (name "unconnected-(USB-TX1+-PadA2)") (class "Default")
      (node (ref "USB") (pin "A2") (pinfunction "TX1+_A2") (pintype "passive+no_connect"))
    )
    (net (code "85") (name "unconnected-(USB-TX1--PadA3)") (class "Default")
      (node (ref "USB") (pin "A3") (pinfunction "TX1-_A3") (pintype "passive+no_connect"))
    )
    (net (code "86") (name "unconnected-(USB-TX2+-PadB2)") (class "Default")
      (node (ref "USB") (pin "B2") (pinfunction "TX2+_B2") (pintype "passive+no_connect"))
    )
    (net (code "87") (name "unconnected-(USB-TX2--PadB3)") (class "Default")
      (node (ref "USB") (pin "B3") (pinfunction "TX2-_B3") (pintype "passive+no_connect"))
    )
  )
)
